# CAN_TRAN.net
KiCad netlist of a schematic drawn in Altium Designer
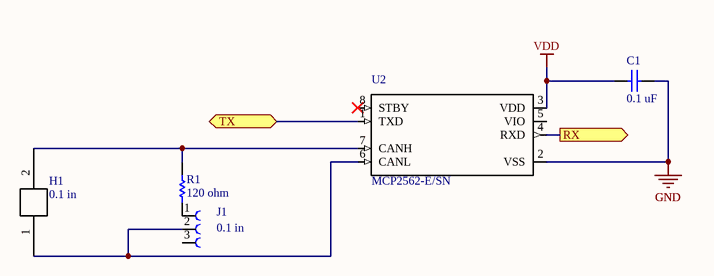
[diagram p0: CAN TRAN.SchDoc]

(export (version "E")
  (design (tool "Eeschema 10.0.6"))
  (components
    (comp (ref "C1")
      (value "0.1 uF")
      (footprint "CAPC0805(2012)130_N")
      (description "CAP 390pF 200V ±5% 0805 (2012 Metric) Thickness 1.3mm SMD")
      (fields (field (name "TOLERANCE") "Â±5%"))
      (libsource (lib "Altium Content Vault") (part "CAP"))
    )
    (comp (ref "H1")
      (value "0.1 in")
      (footprint "PCBComponent_1")
      (description "Molex micro-fit 3.0. Molex P/N 0430450227")
      (libsource (lib "Molex Micro-Fit 3.0") (part "0430450227"))
    )
    (comp (ref "J1")
      (value "0.1 in")
      (footprint "61300311121")
      (description "Board-To-Board Connector, Vertical, WR-PHD Series, Through Hole, Header, 3, 2.54 mm")
      (fields (field (name "MP") "61300311121") (field (name "MF") "Wurth Electronics"))
      (libsource (lib "61300311121") (part "61300311121"))
    )
    (comp (ref "R1")
      (value "120 ohm")
      (footprint "RESC0805(2012)_N")
      (description "160R 0.125W 1% 0805 (2012 Metric)  SMD")
      (fields (field (name "TOLERANCE") "1 %") (field (name "POWER") "0.125 W"))
      (libsource (lib "Altium Content Vault") (part "RES"))
    )
    (comp (ref "U2")
      (value "MCP2562-E/SN")
      (footprint "SOIC127P600X175-8N")
      (description "Microchip MCP2562-E/SN, CAN Transceiver 1MBps 1-channel IEC 61000-4-2, 8-Pin SOIC")
      (fields (field (name "MF") "Microchip"))
      (libsource (lib "CAN Tranceiver (2)") (part "MCP2562-E/SN"))
    )
  )
  (nets
    (net (code "1") (name "/RX") (class "Default")
      (node (ref "U2") (pin "4") (pinfunction "RXD_4") (pintype "output"))
    )
    (net (code "2") (name "/TX") (class "Default")
      (node (ref "U2") (pin "1") (pinfunction "TXD_1") (pintype "input"))
    )
    (net (code "3") (name "GND") (class "Default")
      (node (ref "C1") (pin "1") (pinfunction "1_1") (pintype "passive"))
      (node (ref "U2") (pin "2") (pinfunction "VSS_2") (pintype "power_in"))
    )
    (net (code "4") (name "Net-(J1-Pad1)") (class "Default")
      (node (ref "J1") (pin "1") (pinfunction "1_1") (pintype "passive"))
      (node (ref "R1") (pin "1") (pinfunction "1_1") (pintype "passive"))
    )
    (net (code "5") (name "Net-(U2-CANH)") (class "Default")
      (node (ref "H1") (pin "2") (pintype "passive"))
      (node (ref "R1") (pin "2") (pinfunction "2_2") (pintype "passive"))
      (node (ref "U2") (pin "7") (pinfunction "CANH_7") (pintype "input"))
    )
    (net (code "6") (name "Net-(U2-CANL)") (class "Default")
      (node (ref "H1") (pin "1") (pintype "passive"))
      (node (ref "J1") (pin "2") (pinfunction "2_2") (pintype "passive"))
      (node (ref "U2") (pin "6") (pinfunction "CANL_6") (pintype "input"))
    )
    (net (code "7") (name "VDD") (class "Default")
      (node (ref "C1") (pin "2") (pinfunction "2_2") (pintype "passive"))
      (node (ref "U2") (pin "3") (pinfunction "VDD_3") (pintype "power_in"))
    )
    (net (code "8") (name "unconnected-(J1-Pad3)") (class "Default")
      (node (ref "J1") (pin "3") (pinfunction "3_3") (pintype "passive"))
    )
    (net (code "9") (name "unconnected-(U2-STBY-Pad8)") (class "Default")
      (node (ref "U2") (pin "8") (pinfunction "STBY_8") (pintype "input+no_connect"))
    )
    (net (code "10") (name "unconnected-(U2-VIO-Pad5)") (class "Default")
      (node (ref "U2") (pin "5") (pinfunction "VIO_5") (pintype "power_in"))
    )
  )
)
